# RAM.net
KiCad netlist of a schematic drawn in EAGLE
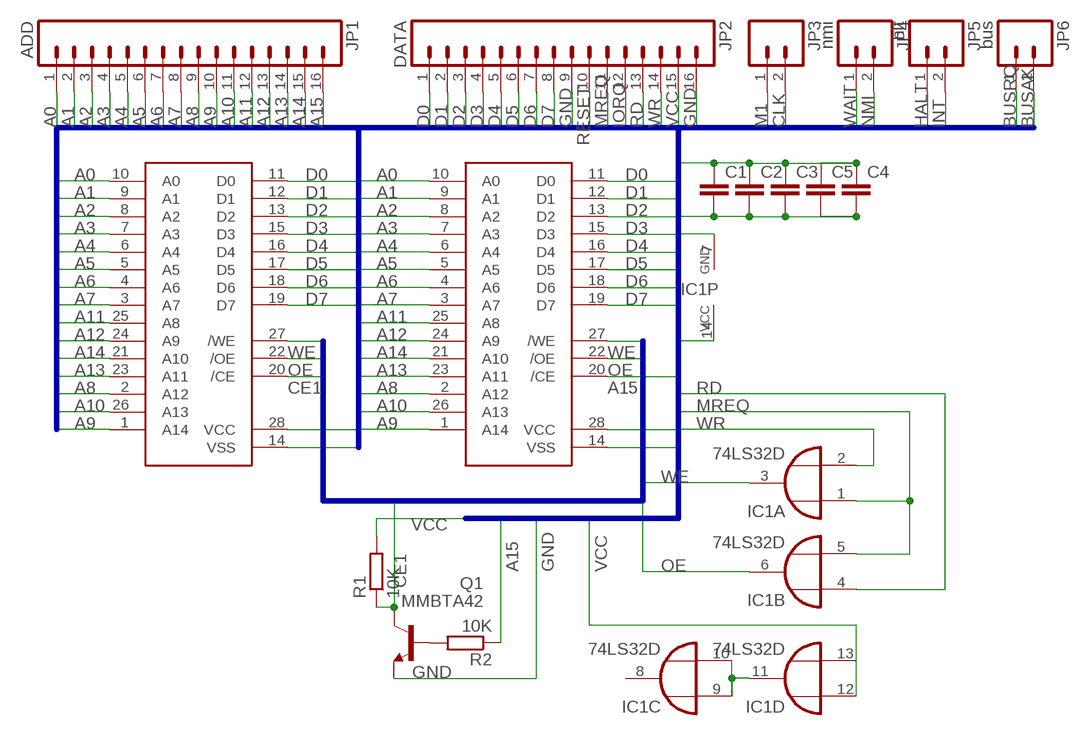
[diagram p0: schematic, sheet 1]

(export (version "E")
  (design (tool "Eeschema 10.0.6"))
  (components
    (comp (ref "C1")
      (value "C-EUC0805")
      (footprint "eagle-import:C0805")
      (libsource (lib "eagle-import") (part "C-EUC0805"))
    )
    (comp (ref "C2")
      (value "C-EUC0805")
      (footprint "eagle-import:C0805")
      (libsource (lib "eagle-import") (part "C-EUC0805"))
    )
    (comp (ref "C3")
      (value "C-EUC0805")
      (footprint "eagle-import:C0805")
      (libsource (lib "eagle-import") (part "C-EUC0805"))
    )
    (comp (ref "C4")
      (value "C-EUC0805")
      (footprint "eagle-import:C0805")
      (libsource (lib "eagle-import") (part "C-EUC0805"))
    )
    (comp (ref "C5")
      (value "C-EUC0805")
      (footprint "eagle-import:C0805")
      (libsource (lib "eagle-import") (part "C-EUC0805"))
    )
    (comp (ref "IC1")
      (value "74LS32D")
      (footprint "eagle-import:SO14")
      (libsource (lib "eagle-import") (part "7432DLS"))
    )
    (comp (ref "JP1")
      (value "ADD")
      (footprint "eagle-import:1X16")
      (libsource (lib "eagle-import") (part "M16PTH"))
    )
    (comp (ref "JP2")
      (value "DATA")
      (footprint "eagle-import:1X16")
      (libsource (lib "eagle-import") (part "M16PTH"))
    )
    (comp (ref "JP3")
      (value "M02PTH")
      (footprint "eagle-import:1X02")
      (libsource (lib "eagle-import") (part "M02PTH"))
    )
    (comp (ref "JP4")
      (value "nmi")
      (footprint "eagle-import:1X02")
      (libsource (lib "eagle-import") (part "M02PTH"))
    )
    (comp (ref "JP5")
      (value "hlt")
      (footprint "eagle-import:1X02")
      (libsource (lib "eagle-import") (part "M02PTH"))
    )
    (comp (ref "JP6")
      (value "bus")
      (footprint "eagle-import:1X02")
      (libsource (lib "eagle-import") (part "M02PTH"))
    )
    (comp (ref "Q1")
      (value "MMBTA42")
      (footprint "eagle-import:SOT23")
      (libsource (lib "eagle-import") (part "MMBTA42"))
    )
    (comp (ref "R1")
      (value "10K")
      (footprint "eagle-import:M0805")
      (libsource (lib "eagle-import") (part "R-EU_M0805"))
    )
    (comp (ref "R2")
      (value "10K")
      (footprint "eagle-import:M0805")
      (libsource (lib "eagle-import") (part "R-EU_M0805"))
    )
    (comp (ref "U$1")
      (value "AS7C256")
      (footprint "eagle-import:SOP28")
      (libsource (lib "eagle-import") (part "AS7C256"))
    )
    (comp (ref "U$2")
      (value "AS7C256")
      (footprint "eagle-import:SOP28")
      (libsource (lib "eagle-import") (part "AS7C256"))
    )
  )
  (nets
    (net (code "1") (name "/A0") (class "Default")
      (node (ref "JP1") (pin "1") (pinfunction "1_1") (pintype "passive"))
      (node (ref "U$1") (pin "10") (pinfunction "A0_10") (pintype "bidirectional"))
      (node (ref "U$2") (pin "10") (pinfunction "A0_10") (pintype "bidirectional"))
    )
    (net (code "2") (name "/A1") (class "Default")
      (node (ref "JP1") (pin "2") (pinfunction "2_2") (pintype "passive"))
      (node (ref "U$1") (pin "9") (pinfunction "A1_9") (pintype "bidirectional"))
      (node (ref "U$2") (pin "9") (pinfunction "A1_9") (pintype "bidirectional"))
    )
    (net (code "3") (name "/A2") (class "Default")
      (node (ref "JP1") (pin "3") (pinfunction "3_3") (pintype "passive"))
      (node (ref "U$1") (pin "8") (pinfunction "A2_8") (pintype "bidirectional"))
      (node (ref "U$2") (pin "8") (pinfunction "A2_8") (pintype "bidirectional"))
    )
    (net (code "4") (name "/A3") (class "Default")
      (node (ref "JP1") (pin "4") (pinfunction "4_4") (pintype "passive"))
      (node (ref "U$1") (pin "7") (pinfunction "A3_7") (pintype "bidirectional"))
      (node (ref "U$2") (pin "7") (pinfunction "A3_7") (pintype "bidirectional"))
    )
    (net (code "5") (name "/A4") (class "Default")
      (node (ref "JP1") (pin "5") (pinfunction "5_5") (pintype "passive"))
      (node (ref "U$1") (pin "6") (pinfunction "A4_6") (pintype "bidirectional"))
      (node (ref "U$2") (pin "6") (pinfunction "A4_6") (pintype "bidirectional"))
    )
    (net (code "6") (name "/A5") (class "Default")
      (node (ref "JP1") (pin "6") (pinfunction "6_6") (pintype "passive"))
      (node (ref "U$1") (pin "5") (pinfunction "A5_5") (pintype "bidirectional"))
      (node (ref "U$2") (pin "5") (pinfunction "A5_5") (pintype "bidirectional"))
    )
    (net (code "7") (name "/A6") (class "Default")
      (node (ref "JP1") (pin "7") (pinfunction "7_7") (pintype "passive"))
      (node (ref "U$1") (pin "4") (pinfunction "A6_4") (pintype "bidirectional"))
      (node (ref "U$2") (pin "4") (pinfunction "A6_4") (pintype "bidirectional"))
    )
    (net (code "8") (name "/A7") (class "Default")
      (node (ref "JP1") (pin "8") (pinfunction "8_8") (pintype "passive"))
      (node (ref "U$1") (pin "3") (pinfunction "A7_3") (pintype "bidirectional"))
      (node (ref "U$2") (pin "3") (pinfunction "A7_3") (pintype "bidirectional"))
    )
    (net (code "9") (name "/A8") (class "Default")
      (node (ref "JP1") (pin "9") (pinfunction "9_9") (pintype "passive"))
      (node (ref "U$1") (pin "2") (pinfunction "A12_2") (pintype "bidirectional"))
      (node (ref "U$2") (pin "2") (pinfunction "A12_2") (pintype "bidirectional"))
    )
    (net (code "10") (name "/A9") (class "Default")
      (node (ref "JP1") (pin "10") (pinfunction "10_10") (pintype "passive"))
      (node (ref "U$1") (pin "1") (pinfunction "A14_1") (pintype "bidirectional"))
      (node (ref "U$2") (pin "1") (pinfunction "A14_1") (pintype "bidirectional"))
    )
    (net (code "11") (name "/A10") (class "Default")
      (node (ref "JP1") (pin "11") (pinfunction "11_11") (pintype "passive"))
      (node (ref "U$1") (pin "26") (pinfunction "A13_26") (pintype "bidirectional"))
      (node (ref "U$2") (pin "26") (pinfunction "A13_26") (pintype "bidirectional"))
    )
    (net (code "12") (name "/A11") (class "Default")
      (node (ref "JP1") (pin "12") (pinfunction "12_12") (pintype "passive"))
      (node (ref "U$1") (pin "25") (pinfunction "A8_25") (pintype "bidirectional"))
      (node (ref "U$2") (pin "25") (pinfunction "A8_25") (pintype "bidirectional"))
    )
    (net (code "13") (name "/A12") (class "Default")
      (node (ref "JP1") (pin "13") (pinfunction "13_13") (pintype "passive"))
      (node (ref "U$1") (pin "24") (pinfunction "A9_24") (pintype "bidirectional"))
      (node (ref "U$2") (pin "24") (pinfunction "A9_24") (pintype "bidirectional"))
    )
    (net (code "14") (name "/A13") (class "Default")
      (node (ref "JP1") (pin "14") (pinfunction "14_14") (pintype "passive"))
      (node (ref "U$1") (pin "23") (pinfunction "A11_23") (pintype "bidirectional"))
      (node (ref "U$2") (pin "23") (pinfunction "A11_23") (pintype "bidirectional"))
    )
    (net (code "15") (name "/A14") (class "Default")
      (node (ref "JP1") (pin "15") (pinfunction "15_15") (pintype "passive"))
      (node (ref "U$1") (pin "21") (pinfunction "A10_21") (pintype "bidirectional"))
      (node (ref "U$2") (pin "21") (pinfunction "A10_21") (pintype "bidirectional"))
    )
    (net (code "16") (name "/A15") (class "Default")
      (node (ref "JP1") (pin "16") (pinfunction "16_16") (pintype "passive"))
      (node (ref "R2") (pin "1") (pinfunction "1_1") (pintype "passive"))
      (node (ref "U$2") (pin "20") (pinfunction "/CE_20") (pintype "bidirectional"))
    )
    (net (code "17") (name "/BUSAK") (class "Default")
      (node (ref "JP6") (pin "2") (pinfunction "2_2") (pintype "passive"))
    )
    (net (code "18") (name "/BUSRQ") (class "Default")
      (node (ref "JP6") (pin "1") (pinfunction "1_1") (pintype "passive"))
    )
    (net (code "19") (name "/CE1") (class "Default")
      (node (ref "Q1") (pin "3") (pinfunction "C_3") (pintype "passive"))
      (node (ref "R1") (pin "1") (pinfunction "1_1") (pintype "passive"))
      (node (ref "U$1") (pin "20") (pinfunction "/CE_20") (pintype "bidirectional"))
    )
    (net (code "20") (name "/CLK") (class "Default")
      (node (ref "JP3") (pin "2") (pinfunction "2_2") (pintype "passive"))
    )
    (net (code "21") (name "/D0") (class "Default")
      (node (ref "JP2") (pin "1") (pinfunction "1_1") (pintype "passive"))
      (node (ref "U$1") (pin "11") (pinfunction "D0_11") (pintype "bidirectional"))
      (node (ref "U$2") (pin "11") (pinfunction "D0_11") (pintype "bidirectional"))
    )
    (net (code "22") (name "/D1") (class "Default")
      (node (ref "JP2") (pin "2") (pinfunction "2_2") (pintype "passive"))
      (node (ref "U$1") (pin "12") (pinfunction "D1_12") (pintype "bidirectional"))
      (node (ref "U$2") (pin "12") (pinfunction "D1_12") (pintype "bidirectional"))
    )
    (net (code "23") (name "/D2") (class "Default")
      (node (ref "JP2") (pin "3") (pinfunction "3_3") (pintype "passive"))
      (node (ref "U$1") (pin "13") (pinfunction "D2_13") (pintype "bidirectional"))
      (node (ref "U$2") (pin "13") (pinfunction "D2_13") (pintype "bidirectional"))
    )
    (net (code "24") (name "/D3") (class "Default")
      (node (ref "JP2") (pin "4") (pinfunction "4_4") (pintype "passive"))
      (node (ref "U$1") (pin "15") (pinfunction "D3_15") (pintype "bidirectional"))
      (node (ref "U$2") (pin "15") (pinfunction "D3_15") (pintype "bidirectional"))
    )
    (net (code "25") (name "/D4") (class "Default")
      (node (ref "JP2") (pin "5") (pinfunction "5_5") (pintype "passive"))
      (node (ref "U$1") (pin "16") (pinfunction "D4_16") (pintype "bidirectional"))
      (node (ref "U$2") (pin "16") (pinfunction "D4_16") (pintype "bidirectional"))
    )
    (net (code "26") (name "/D5") (class "Default")
      (node (ref "JP2") (pin "6") (pinfunction "6_6") (pintype "passive"))
      (node (ref "U$1") (pin "17") (pinfunction "D5_17") (pintype "bidirectional"))
      (node (ref "U$2") (pin "17") (pinfunction "D5_17") (pintype "bidirectional"))
    )
    (net (code "27") (name "/D6") (class "Default")
      (node (ref "JP2") (pin "7") (pinfunction "7_7") (pintype "passive"))
      (node (ref "U$1") (pin "18") (pinfunction "D6_18") (pintype "bidirectional"))
      (node (ref "U$2") (pin "18") (pinfunction "D6_18") (pintype "bidirectional"))
    )
    (net (code "28") (name "/D7") (class "Default")
      (node (ref "JP2") (pin "8") (pinfunction "8_8") (pintype "passive"))
      (node (ref "U$1") (pin "19") (pinfunction "D7_19") (pintype "bidirectional"))
      (node (ref "U$2") (pin "19") (pinfunction "D7_19") (pintype "bidirectional"))
    )
    (net (code "29") (name "/GND") (class "Default")
      (node (ref "C1") (pin "2") (pinfunction "2_2") (pintype "passive"))
      (node (ref "C2") (pin "2") (pinfunction "2_2") (pintype "passive"))
      (node (ref "C3") (pin "2") (pinfunction "2_2") (pintype "passive"))
      (node (ref "C4") (pin "2") (pinfunction "2_2") (pintype "passive"))
      (node (ref "C5") (pin "2") (pinfunction "2_2") (pintype "passive"))
      (node (ref "IC1") (pin "7") (pinfunction "GND_7") (pintype "power_in"))
      (node (ref "JP2") (pin "16") (pinfunction "16_16") (pintype "passive"))
      (node (ref "JP2") (pin "9") (pinfunction "9_9") (pintype "passive"))
      (node (ref "Q1") (pin "2") (pinfunction "E_2") (pintype "passive"))
      (node (ref "U$1") (pin "14") (pinfunction "VSS_14") (pintype "bidirectional"))
      (node (ref "U$2") (pin "14") (pinfunction "VSS_14") (pintype "bidirectional"))
    )
    (net (code "30") (name "/HALT") (class "Default")
      (node (ref "JP5") (pin "1") (pinfunction "1_1") (pintype "passive"))
    )
    (net (code "31") (name "/INT") (class "Default")
      (node (ref "JP5") (pin "2") (pinfunction "2_2") (pintype "passive"))
    )
    (net (code "32") (name "/IORQ") (class "Default")
      (node (ref "JP2") (pin "12") (pinfunction "12_12") (pintype "passive"))
    )
    (net (code "33") (name "/M1") (class "Default")
      (node (ref "JP3") (pin "1") (pinfunction "1_1") (pintype "passive"))
    )
    (net (code "34") (name "/MREQ") (class "Default")
      (node (ref "IC1") (pin "1") (pinfunction "I0_1") (pintype "input"))
      (node (ref "IC1") (pin "5") (pinfunction "I1_5") (pintype "input"))
      (node (ref "JP2") (pin "11") (pinfunction "11_11") (pintype "passive"))
    )
    (net (code "35") (name "/NMI") (class "Default")
      (node (ref "JP4") (pin "2") (pinfunction "2_2") (pintype "passive"))
    )
    (net (code "36") (name "/OE") (class "Default")
      (node (ref "IC1") (pin "6") (pinfunction "O_6") (pintype "output"))
      (node (ref "U$1") (pin "22") (pinfunction "/OE_22") (pintype "bidirectional"))
      (node (ref "U$2") (pin "22") (pinfunction "/OE_22") (pintype "bidirectional"))
    )
    (net (code "37") (name "/RD") (class "Default")
      (node (ref "IC1") (pin "4") (pinfunction "I0_4") (pintype "input"))
      (node (ref "JP2") (pin "13") (pinfunction "13_13") (pintype "passive"))
    )
    (net (code "38") (name "/RESET") (class "Default")
      (node (ref "JP2") (pin "10") (pinfunction "10_10") (pintype "passive"))
    )
    (net (code "39") (name "/VCC") (class "Default")
      (node (ref "C1") (pin "1") (pinfunction "1_1") (pintype "passive"))
      (node (ref "C2") (pin "1") (pinfunction "1_1") (pintype "passive"))
      (node (ref "C3") (pin "1") (pinfunction "1_1") (pintype "passive"))
      (node (ref "C4") (pin "1") (pinfunction "1_1") (pintype "passive"))
      (node (ref "C5") (pin "1") (pinfunction "1_1") (pintype "passive"))
      (node (ref "IC1") (pin "12") (pinfunction "I0_12") (pintype "input"))
      (node (ref "IC1") (pin "13") (pinfunction "I1_13") (pintype "input"))
      (node (ref "IC1") (pin "14") (pinfunction "VCC_14") (pintype "power_in"))
      (node (ref "JP2") (pin "15") (pinfunction "15_15") (pintype "passive"))
      (node (ref "R1") (pin "2") (pinfunction "2_2") (pintype "passive"))
      (node (ref "U$1") (pin "28") (pinfunction "VCC_28") (pintype "bidirectional"))
      (node (ref "U$2") (pin "28") (pinfunction "VCC_28") (pintype "bidirectional"))
    )
    (net (code "40") (name "/WAIT") (class "Default")
      (node (ref "JP4") (pin "1") (pinfunction "1_1") (pintype "passive"))
    )
    (net (code "41") (name "/WE") (class "Default")
      (node (ref "IC1") (pin "3") (pinfunction "O_3") (pintype "output"))
      (node (ref "U$1") (pin "27") (pinfunction "/WE_27") (pintype "bidirectional"))
      (node (ref "U$2") (pin "27") (pinfunction "/WE_27") (pintype "bidirectional"))
    )
    (net (code "42") (name "/WR") (class "Default")
      (node (ref "IC1") (pin "2") (pinfunction "I1_2") (pintype "input"))
      (node (ref "JP2") (pin "14") (pinfunction "14_14") (pintype "passive"))
    )
    (net (code "43") (name "Net-(IC1C-I0)") (class "Default")
      (node (ref "IC1") (pin "10") (pinfunction "I1_10") (pintype "input"))
      (node (ref "IC1") (pin "11") (pinfunction "O_11") (pintype "output"))
      (node (ref "IC1") (pin "9") (pinfunction "I0_9") (pintype "input"))
    )
    (net (code "44") (name "Net-(Q1-B)") (class "Default")
      (node (ref "Q1") (pin "1") (pinfunction "B_1") (pintype "passive"))
      (node (ref "R2") (pin "2") (pinfunction "2_2") (pintype "passive"))
    )
    (net (code "45") (name "unconnected-(IC1C-O-Pad8)") (class "Default")
      (node (ref "IC1") (pin "8") (pinfunction "O_8") (pintype "output"))
    )
  )
)
